# PD_USB.net
KiCad netlist of a schematic drawn in Altium Designer
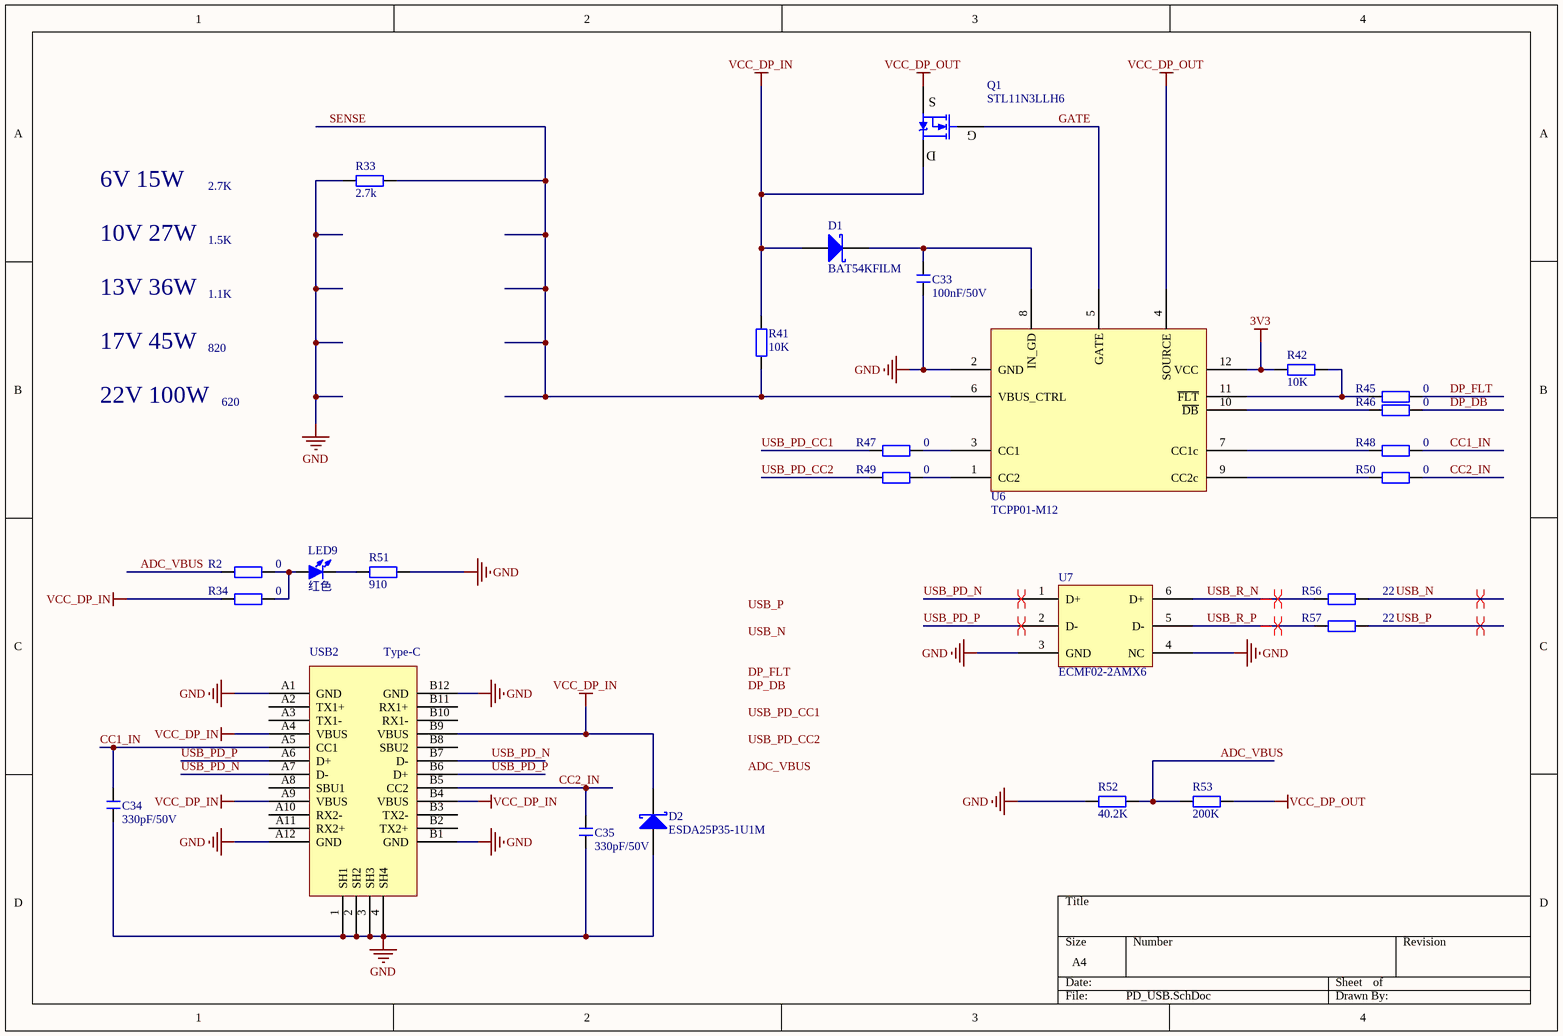
[diagram p0: PD_USB.SchDoc]

(export (version "E")
  (design (tool "Eeschema 10.0.6"))
  (components
    (comp (ref "C33")
      (value "100nF/50V")
      (footprint "C 0402_L")
      (description "贴片电容")
      (libsource (lib "3.1   - 电阻-电容-电感") (part "C"))
    )
    (comp (ref "C34")
      (value "330pF/50V")
      (footprint "C 0402_L")
      (description "贴片电容")
      (libsource (lib "3.1   - 电阻-电容-电感") (part "C"))
    )
    (comp (ref "C35")
      (value "330pF/50V")
      (footprint "C 0402_L")
      (description "贴片电容")
      (libsource (lib "3.1   - 电阻-电容-电感") (part "C"))
    )
    (comp (ref "D1")
      (value "BAT54KFILM")
      (footprint "BAT54KFILM")
      (description "Schottky Diode")
      (libsource (lib "Miscellaneous Devices") (part "D Schottky"))
    )
    (comp (ref "D2")
      (value "ESDA25P35-1U1M")
      (footprint "ESDA25P35-1U1M")
      (description "Schottky Diode")
      (libsource (lib "Miscellaneous Devices") (part "D Schottky"))
    )
    (comp (ref "LED9")
      (value "红色")
      (footprint "LED")
      (description "C84267")
      (libsource (lib "9.1   - LED") (part "LED-SMD"))
    )
    (comp (ref "Q1")
      (value "STL11N3LLH6")
      (footprint "STL11N3LLH6")
      (description "N沟道场效应管")
      (libsource (lib "6.1   - 场效应管-可控硅") (part "SI2302"))
    )
    (comp (ref "R2")
      (value "0")
      (footprint "R 0402_L")
      (description "贴片电阻")
      (libsource (lib "3.1   - 电阻-电容-电感") (part "R"))
    )
    (comp (ref "R33")
      (value "2.7k")
      (footprint "R 0402_L")
      (description "贴片电阻")
      (libsource (lib "3.1   - 电阻-电容-电感") (part "R"))
    )
    (comp (ref "R34")
      (value "0")
      (footprint "R 0402_L")
      (description "贴片电阻")
      (libsource (lib "3.1   - 电阻-电容-电感") (part "R"))
    )
    (comp (ref "R41")
      (value "10K")
      (footprint "R 0402_L")
      (description "贴片电阻")
      (libsource (lib "3.1   - 电阻-电容-电感") (part "R"))
    )
    (comp (ref "R42")
      (value "10K")
      (footprint "R 0402_L")
      (description "贴片电阻")
      (libsource (lib "3.1   - 电阻-电容-电感") (part "R"))
    )
    (comp (ref "R45")
      (value "0")
      (footprint "R 0402_L")
      (description "贴片电阻")
      (libsource (lib "3.1   - 电阻-电容-电感") (part "R"))
    )
    (comp (ref "R46")
      (value "0")
      (footprint "R 0402_L")
      (description "贴片电阻")
      (libsource (lib "3.1   - 电阻-电容-电感") (part "R"))
    )
    (comp (ref "R47")
      (value "0")
      (footprint "R 0402_L")
      (description "贴片电阻")
      (libsource (lib "3.1   - 电阻-电容-电感") (part "R"))
    )
    (comp (ref "R48")
      (value "0")
      (footprint "R 0402_L")
      (description "贴片电阻")
      (libsource (lib "3.1   - 电阻-电容-电感") (part "R"))
    )
    (comp (ref "R49")
      (value "0")
      (footprint "R 0402_L")
      (description "贴片电阻")
      (libsource (lib "3.1   - 电阻-电容-电感") (part "R"))
    )
    (comp (ref "R50")
      (value "0")
      (footprint "R 0402_L")
      (description "贴片电阻")
      (libsource (lib "3.1   - 电阻-电容-电感") (part "R"))
    )
    (comp (ref "R51")
      (value "910")
      (footprint "R 0402_L")
      (description "贴片电阻 0402 5%")
      (libsource (lib "3.1   - 电阻-电容-电感") (part "R"))
    )
    (comp (ref "R52")
      (value "40.2K")
      (footprint "R 0402_L")
      (description "贴片电阻")
      (libsource (lib "3.1   - 电阻-电容-电感") (part "R"))
    )
    (comp (ref "R53")
      (value "200K")
      (footprint "R 0402_L")
      (description "贴片电阻")
      (libsource (lib "3.1   - 电阻-电容-电感") (part "R"))
    )
    (comp (ref "R56")
      (value "22")
      (footprint "R 0402_L")
      (description "贴片电阻")
      (libsource (lib "3.1   - 电阻-电容-电感") (part "R"))
    )
    (comp (ref "R57")
      (value "22")
      (footprint "R 0402_L")
      (description "贴片电阻")
      (libsource (lib "3.1   - 电阻-电容-电感") (part "R"))
    )
    (comp (ref "U6")
      (value "TCPP01-M12")
      (footprint "TCPP01-M12")
      (libsource (lib "2021-04-22_13-53-57") (part "TCPP01-M12"))
    )
    (comp (ref "U7")
      (value "ECMF02-2AMX6")
      (footprint "ECMF02-2AMX6")
      (libsource (lib "2021-04-22_13-53-57") (part "ECMF02-2AMX6"))
    )
    (comp (ref "USB2")
      (value "Type-C")
      (footprint "Type-c接口")
      (libsource (lib "MyPcbLib") (part "USB-Type-C-TOP"))
    )
  )
  (nets
    (net (code "1") (name "/ADC_VBUS") (class "Default")
      (node (ref "R2") (pin "1") (pinfunction "1_1") (pintype "passive"))
      (node (ref "R52") (pin "1") (pinfunction "1_1") (pintype "passive"))
      (node (ref "R53") (pin "2") (pinfunction "2_2") (pintype "passive"))
    )
    (net (code "2") (name "/CC1_IN") (class "Default")
      (node (ref "C34") (pin "2") (pinfunction "2_2") (pintype "passive"))
      (node (ref "R48") (pin "2") (pinfunction "2_2") (pintype "passive"))
      (node (ref "USB2") (pin "A5") (pinfunction "CC1_A5") (pintype "passive"))
    )
    (net (code "3") (name "/CC2_IN") (class "Default")
      (node (ref "C35") (pin "2") (pinfunction "2_2") (pintype "passive"))
      (node (ref "R50") (pin "2") (pinfunction "2_2") (pintype "passive"))
      (node (ref "USB2") (pin "B5") (pinfunction "CC2_B5") (pintype "passive"))
    )
    (net (code "4") (name "/DP_DB") (class "Default")
      (node (ref "R46") (pin "2") (pinfunction "2_2") (pintype "passive"))
    )
    (net (code "5") (name "/DP_FLT") (class "Default")
      (node (ref "R45") (pin "2") (pinfunction "2_2") (pintype "passive"))
    )
    (net (code "6") (name "/GATE") (class "Default")
      (node (ref "Q1") (pin "1") (pinfunction "G_1") (pintype "passive"))
      (node (ref "U6") (pin "5") (pinfunction "GATE_5") (pintype "passive"))
    )
    (net (code "7") (name "/SENSE") (class "Default")
      (node (ref "R33") (pin "2") (pinfunction "2_2") (pintype "passive"))
      (node (ref "R41") (pin "1") (pinfunction "1_1") (pintype "passive"))
      (node (ref "U6") (pin "6") (pinfunction "VBUS_CTRL_6") (pintype "passive"))
    )
    (net (code "8") (name "/USB_N") (class "Default")
      (node (ref "R56") (pin "1") (pinfunction "1_1") (pintype "passive"))
    )
    (net (code "9") (name "/USB_P") (class "Default")
      (node (ref "R57") (pin "1") (pinfunction "1_1") (pintype "passive"))
    )
    (net (code "10") (name "/USB_PD_CC1") (class "Default")
      (node (ref "R47") (pin "1") (pinfunction "1_1") (pintype "passive"))
    )
    (net (code "11") (name "/USB_PD_CC2") (class "Default")
      (node (ref "R49") (pin "1") (pinfunction "1_1") (pintype "passive"))
    )
    (net (code "12") (name "/USB_PD_N") (class "Default")
      (node (ref "U7") (pin "1") (pinfunction "D+_1") (pintype "passive"))
      (node (ref "USB2") (pin "A7") (pinfunction "D-_A7") (pintype "passive"))
      (node (ref "USB2") (pin "B7") (pinfunction "D-_B7") (pintype "passive"))
    )
    (net (code "13") (name "/USB_PD_P") (class "Default")
      (node (ref "U7") (pin "2") (pinfunction "D-_2") (pintype "passive"))
      (node (ref "USB2") (pin "A6") (pinfunction "D+_A6") (pintype "passive"))
      (node (ref "USB2") (pin "B6") (pinfunction "D+_B6") (pintype "passive"))
    )
    (net (code "14") (name "/USB_R_N") (class "Default")
      (node (ref "R56") (pin "2") (pinfunction "2_2") (pintype "passive"))
      (node (ref "U7") (pin "6") (pinfunction "D+_6") (pintype "passive"))
    )
    (net (code "15") (name "/USB_R_P") (class "Default")
      (node (ref "R57") (pin "2") (pinfunction "2_2") (pintype "passive"))
      (node (ref "U7") (pin "5") (pinfunction "D-_5") (pintype "passive"))
    )
    (net (code "16") (name "3V3") (class "Default")
      (node (ref "R42") (pin "2") (pinfunction "2_2") (pintype "passive"))
      (node (ref "U6") (pin "12") (pinfunction "VCC_12") (pintype "passive"))
    )
    (net (code "17") (name "GND") (class "Default")
      (node (ref "C33") (pin "1") (pinfunction "1_1") (pintype "passive"))
      (node (ref "C34") (pin "1") (pinfunction "1_1") (pintype "passive"))
      (node (ref "C35") (pin "1") (pinfunction "1_1") (pintype "passive"))
      (node (ref "D2") (pin "1") (pinfunction "A_1") (pintype "passive"))
      (node (ref "R33") (pin "1") (pinfunction "1_1") (pintype "passive"))
      (node (ref "R51") (pin "1") (pinfunction "1_1") (pintype "passive"))
      (node (ref "R52") (pin "2") (pinfunction "2_2") (pintype "passive"))
      (node (ref "U6") (pin "2") (pinfunction "GND_2") (pintype "passive"))
      (node (ref "U7") (pin "3") (pinfunction "GND_3") (pintype "passive"))
      (node (ref "U7") (pin "4") (pinfunction "NC_4") (pintype "passive"))
      (node (ref "USB2") (pin "1") (pinfunction "SH1_1") (pintype "passive"))
      (node (ref "USB2") (pin "2") (pinfunction "SH2_2") (pintype "passive"))
      (node (ref "USB2") (pin "3") (pinfunction "SH3_3") (pintype "passive"))
      (node (ref "USB2") (pin "4") (pinfunction "SH4_4") (pintype "passive"))
      (node (ref "USB2") (pin "A1") (pinfunction "GND_A1") (pintype "passive"))
      (node (ref "USB2") (pin "A12") (pinfunction "GND_A12") (pintype "passive"))
      (node (ref "USB2") (pin "B1") (pinfunction "GND_B1") (pintype "passive"))
      (node (ref "USB2") (pin "B12") (pinfunction "GND_B12") (pintype "passive"))
    )
    (net (code "18") (name "Net-(D1-K)") (class "Default")
      (node (ref "C33") (pin "2") (pinfunction "2_2") (pintype "passive"))
      (node (ref "D1") (pin "2") (pinfunction "K_2") (pintype "passive"))
      (node (ref "U6") (pin "8") (pinfunction "IN_GD_8") (pintype "passive"))
    )
    (net (code "19") (name "Net-(LED9-A)") (class "Default")
      (node (ref "LED9") (pin "1") (pinfunction "A_1") (pintype "passive"))
      (node (ref "R2") (pin "2") (pinfunction "2_2") (pintype "passive"))
      (node (ref "R34") (pin "2") (pinfunction "2_2") (pintype "passive"))
    )
    (net (code "20") (name "Net-(LED9-K)") (class "Default")
      (node (ref "LED9") (pin "2") (pinfunction "K_2") (pintype "passive"))
      (node (ref "R51") (pin "2") (pinfunction "2_2") (pintype "passive"))
    )
    (net (code "21") (name "Net-(U6-CC1)") (class "Default")
      (node (ref "R47") (pin "2") (pinfunction "2_2") (pintype "passive"))
      (node (ref "U6") (pin "3") (pinfunction "CC1_3") (pintype "passive"))
    )
    (net (code "22") (name "Net-(U6-CC1c)") (class "Default")
      (node (ref "R48") (pin "1") (pinfunction "1_1") (pintype "passive"))
      (node (ref "U6") (pin "7") (pinfunction "CC1c_7") (pintype "passive"))
    )
    (net (code "23") (name "Net-(U6-CC2)") (class "Default")
      (node (ref "R49") (pin "2") (pinfunction "2_2") (pintype "passive"))
      (node (ref "U6") (pin "1") (pinfunction "CC2_1") (pintype "passive"))
    )
    (net (code "24") (name "Net-(U6-CC2c)") (class "Default")
      (node (ref "R50") (pin "1") (pinfunction "1_1") (pintype "passive"))
      (node (ref "U6") (pin "9") (pinfunction "CC2c_9") (pintype "passive"))
    )
    (net (code "25") (name "Net-(U6-~{DB})") (class "Default")
      (node (ref "R46") (pin "1") (pinfunction "1_1") (pintype "passive"))
      (node (ref "U6") (pin "10") (pinfunction "~{DB}_10") (pintype "passive"))
    )
    (net (code "26") (name "Net-(U6-~{FLT})") (class "Default")
      (node (ref "R42") (pin "1") (pinfunction "1_1") (pintype "passive"))
      (node (ref "R45") (pin "1") (pinfunction "1_1") (pintype "passive"))
      (node (ref "U6") (pin "11") (pinfunction "~{FLT}_11") (pintype "passive"))
    )
    (net (code "27") (name "VCC_DP_IN") (class "Default")
      (node (ref "D1") (pin "1") (pinfunction "A_1") (pintype "passive"))
      (node (ref "D2") (pin "2") (pinfunction "K_2") (pintype "passive"))
      (node (ref "Q1") (pin "3") (pinfunction "D_3") (pintype "passive"))
      (node (ref "R34") (pin "1") (pinfunction "1_1") (pintype "passive"))
      (node (ref "R41") (pin "2") (pinfunction "2_2") (pintype "passive"))
      (node (ref "USB2") (pin "A4") (pinfunction "VBUS_A4") (pintype "passive"))
      (node (ref "USB2") (pin "A9") (pinfunction "VBUS_A9") (pintype "passive"))
      (node (ref "USB2") (pin "B4") (pinfunction "VBUS_B4") (pintype "passive"))
      (node (ref "USB2") (pin "B9") (pinfunction "VBUS_B9") (pintype "passive"))
    )
    (net (code "28") (name "VCC_DP_OUT") (class "Default")
      (node (ref "Q1") (pin "2") (pinfunction "S_2") (pintype "passive"))
      (node (ref "R53") (pin "1") (pinfunction "1_1") (pintype "passive"))
      (node (ref "U6") (pin "4") (pinfunction "SOURCE_4") (pintype "passive"))
    )
    (net (code "29") (name "unconnected-(USB2-RX1+-PadB11)") (class "Default")
      (node (ref "USB2") (pin "B11") (pinfunction "RX1+_B11") (pintype "passive"))
    )
    (net (code "30") (name "unconnected-(USB2-RX1--PadB10)") (class "Default")
      (node (ref "USB2") (pin "B10") (pinfunction "RX1-_B10") (pintype "passive"))
    )
    (net (code "31") (name "unconnected-(USB2-RX2+-PadA11)") (class "Default")
      (node (ref "USB2") (pin "A11") (pinfunction "RX2+_A11") (pintype "passive"))
    )
    (net (code "32") (name "unconnected-(USB2-RX2--PadA10)") (class "Default")
      (node (ref "USB2") (pin "A10") (pinfunction "RX2-_A10") (pintype "passive"))
    )
    (net (code "33") (name "unconnected-(USB2-SBU1-PadA8)") (class "Default")
      (node (ref "USB2") (pin "A8") (pinfunction "SBU1_A8") (pintype "passive"))
    )
    (net (code "34") (name "unconnected-(USB2-SBU2-PadB8)") (class "Default")
      (node (ref "USB2") (pin "B8") (pinfunction "SBU2_B8") (pintype "passive"))
    )
    (net (code "35") (name "unconnected-(USB2-TX1+-PadA2)") (class "Default")
      (node (ref "USB2") (pin "A2") (pinfunction "TX1+_A2") (pintype "passive"))
    )
    (net (code "36") (name "unconnected-(USB2-TX1--PadA3)") (class "Default")
      (node (ref "USB2") (pin "A3") (pinfunction "TX1-_A3") (pintype "passive"))
    )
    (net (code "37") (name "unconnected-(USB2-TX2+-PadB2)") (class "Default")
      (node (ref "USB2") (pin "B2") (pinfunction "TX2+_B2") (pintype "passive"))
    )
    (net (code "38") (name "unconnected-(USB2-TX2--PadB3)") (class "Default")
      (node (ref "USB2") (pin "B3") (pinfunction "TX2-_B3") (pintype "passive"))
    )
  )
)
